# proud.net
KiCad netlist of a schematic drawn in EAGLE
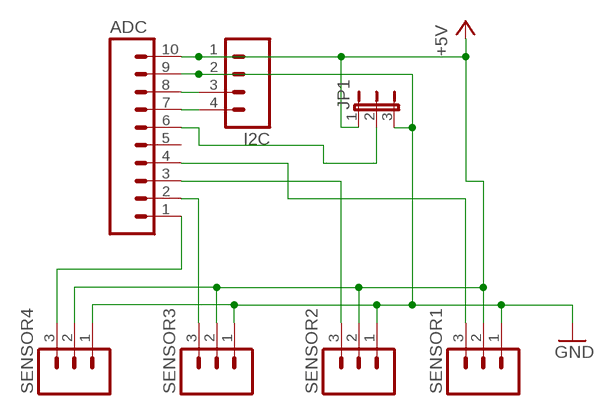
[diagram p0: schematic, sheet 1]

(export (version "E")
  (design (tool "Eeschema 10.0.6"))
  (components
    (comp (ref "ADC")
      (value "M10")
      (footprint "eagle-import:10P")
      (libsource (lib "eagle-import") (part "M10"))
    )
    (comp (ref "I2C")
      (value "M04")
      (footprint "eagle-import:04P")
      (libsource (lib "eagle-import") (part "M04"))
    )
    (comp (ref "JP1")
      (value "JP2E")
      (footprint "eagle-import:JP2")
      (libsource (lib "eagle-import") (part "JP2E"))
    )
    (comp (ref "SENSOR1")
      (value "M03")
      (footprint "eagle-import:03P")
      (libsource (lib "eagle-import") (part "M03"))
    )
    (comp (ref "SENSOR2")
      (value "M03")
      (footprint "eagle-import:03P")
      (libsource (lib "eagle-import") (part "M03"))
    )
    (comp (ref "SENSOR3")
      (value "M03")
      (footprint "eagle-import:03P")
      (libsource (lib "eagle-import") (part "M03"))
    )
    (comp (ref "SENSOR4")
      (value "M03")
      (footprint "eagle-import:03P")
      (libsource (lib "eagle-import") (part "M03"))
    )
  )
  (nets
    (net (code "1") (name "+5V") (class "Default")
      (node (ref "ADC") (pin "10") (pinfunction "10_10") (pintype "passive"))
      (node (ref "I2C") (pin "1") (pinfunction "1_1") (pintype "passive"))
      (node (ref "JP1") (pin "1") (pinfunction "1_1") (pintype "passive"))
      (node (ref "SENSOR1") (pin "2") (pinfunction "2_2") (pintype "passive"))
      (node (ref "SENSOR2") (pin "2") (pinfunction "2_2") (pintype "passive"))
      (node (ref "SENSOR3") (pin "2") (pinfunction "2_2") (pintype "passive"))
      (node (ref "SENSOR4") (pin "2") (pinfunction "2_2") (pintype "passive"))
    )
    (net (code "2") (name "GND") (class "Default")
      (node (ref "ADC") (pin "9") (pinfunction "9_9") (pintype "passive"))
      (node (ref "I2C") (pin "2") (pinfunction "2_2") (pintype "passive"))
      (node (ref "JP1") (pin "3") (pinfunction "3_3") (pintype "passive"))
      (node (ref "SENSOR1") (pin "1") (pinfunction "1_1") (pintype "passive"))
      (node (ref "SENSOR2") (pin "1") (pinfunction "1_1") (pintype "passive"))
      (node (ref "SENSOR3") (pin "1") (pinfunction "1_1") (pintype "passive"))
      (node (ref "SENSOR4") (pin "1") (pinfunction "1_1") (pintype "passive"))
    )
    (net (code "3") (name "Net-(ADC-Pad1)") (class "Default")
      (node (ref "ADC") (pin "1") (pinfunction "1_1") (pintype "passive"))
      (node (ref "SENSOR4") (pin "3") (pinfunction "3_3") (pintype "passive"))
    )
    (net (code "4") (name "Net-(ADC-Pad2)") (class "Default")
      (node (ref "ADC") (pin "2") (pinfunction "2_2") (pintype "passive"))
      (node (ref "SENSOR3") (pin "3") (pinfunction "3_3") (pintype "passive"))
    )
    (net (code "5") (name "Net-(ADC-Pad3)") (class "Default")
      (node (ref "ADC") (pin "3") (pinfunction "3_3") (pintype "passive"))
      (node (ref "SENSOR2") (pin "3") (pinfunction "3_3") (pintype "passive"))
    )
    (net (code "6") (name "Net-(ADC-Pad4)") (class "Default")
      (node (ref "ADC") (pin "4") (pinfunction "4_4") (pintype "passive"))
      (node (ref "SENSOR1") (pin "3") (pinfunction "3_3") (pintype "passive"))
    )
    (net (code "7") (name "Net-(ADC-Pad6)") (class "Default")
      (node (ref "ADC") (pin "6") (pinfunction "6_6") (pintype "passive"))
      (node (ref "JP1") (pin "2") (pinfunction "2_2") (pintype "passive"))
    )
    (net (code "8") (name "Net-(ADC-Pad7)") (class "Default")
      (node (ref "ADC") (pin "7") (pinfunction "7_7") (pintype "passive"))
      (node (ref "I2C") (pin "4") (pinfunction "4_4") (pintype "passive"))
    )
    (net (code "9") (name "Net-(ADC-Pad8)") (class "Default")
      (node (ref "ADC") (pin "8") (pinfunction "8_8") (pintype "passive"))
      (node (ref "I2C") (pin "3") (pinfunction "3_3") (pintype "passive"))
    )
    (net (code "10") (name "unconnected-(ADC-Pad5)") (class "Default")
      (node (ref "ADC") (pin "5") (pinfunction "5_5") (pintype "passive"))
    )
  )
)
